# ESP32_Display-1_28-V1_0.net
KiCad netlist of a schematic drawn in EAGLE
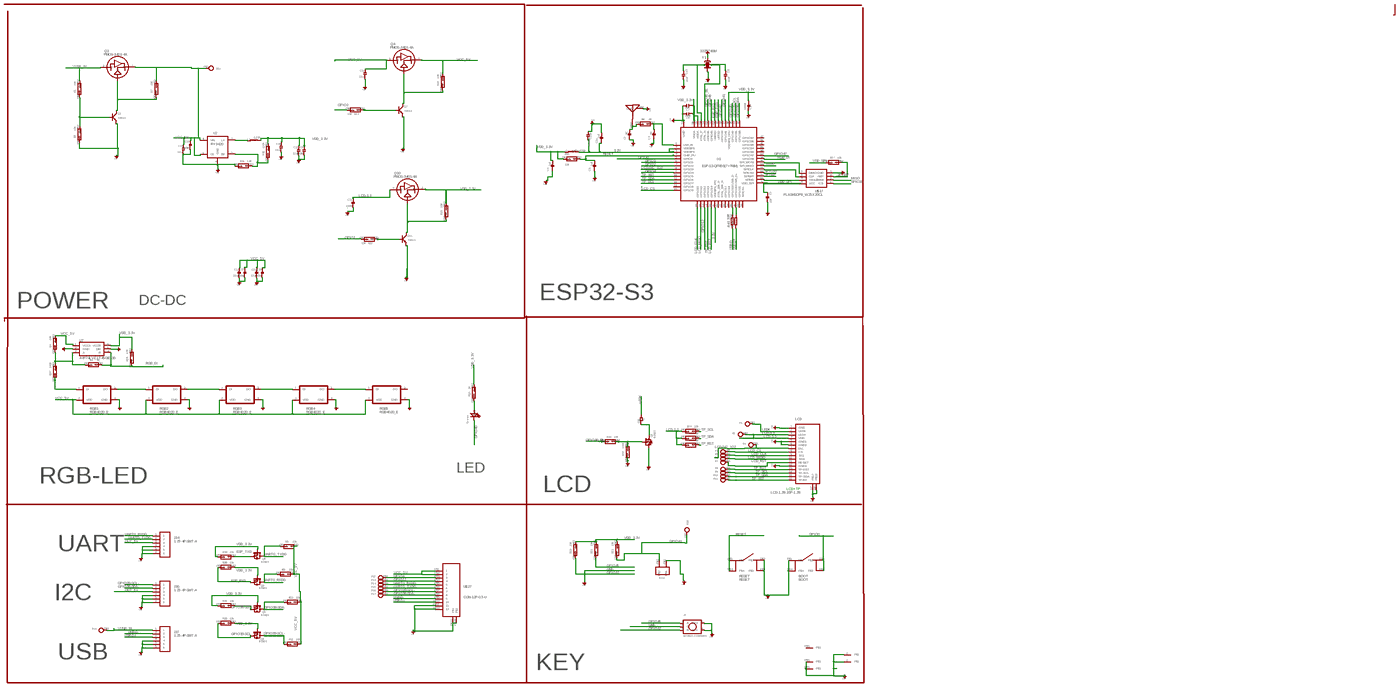
[diagram p0: schematic, sheet 1, overview]
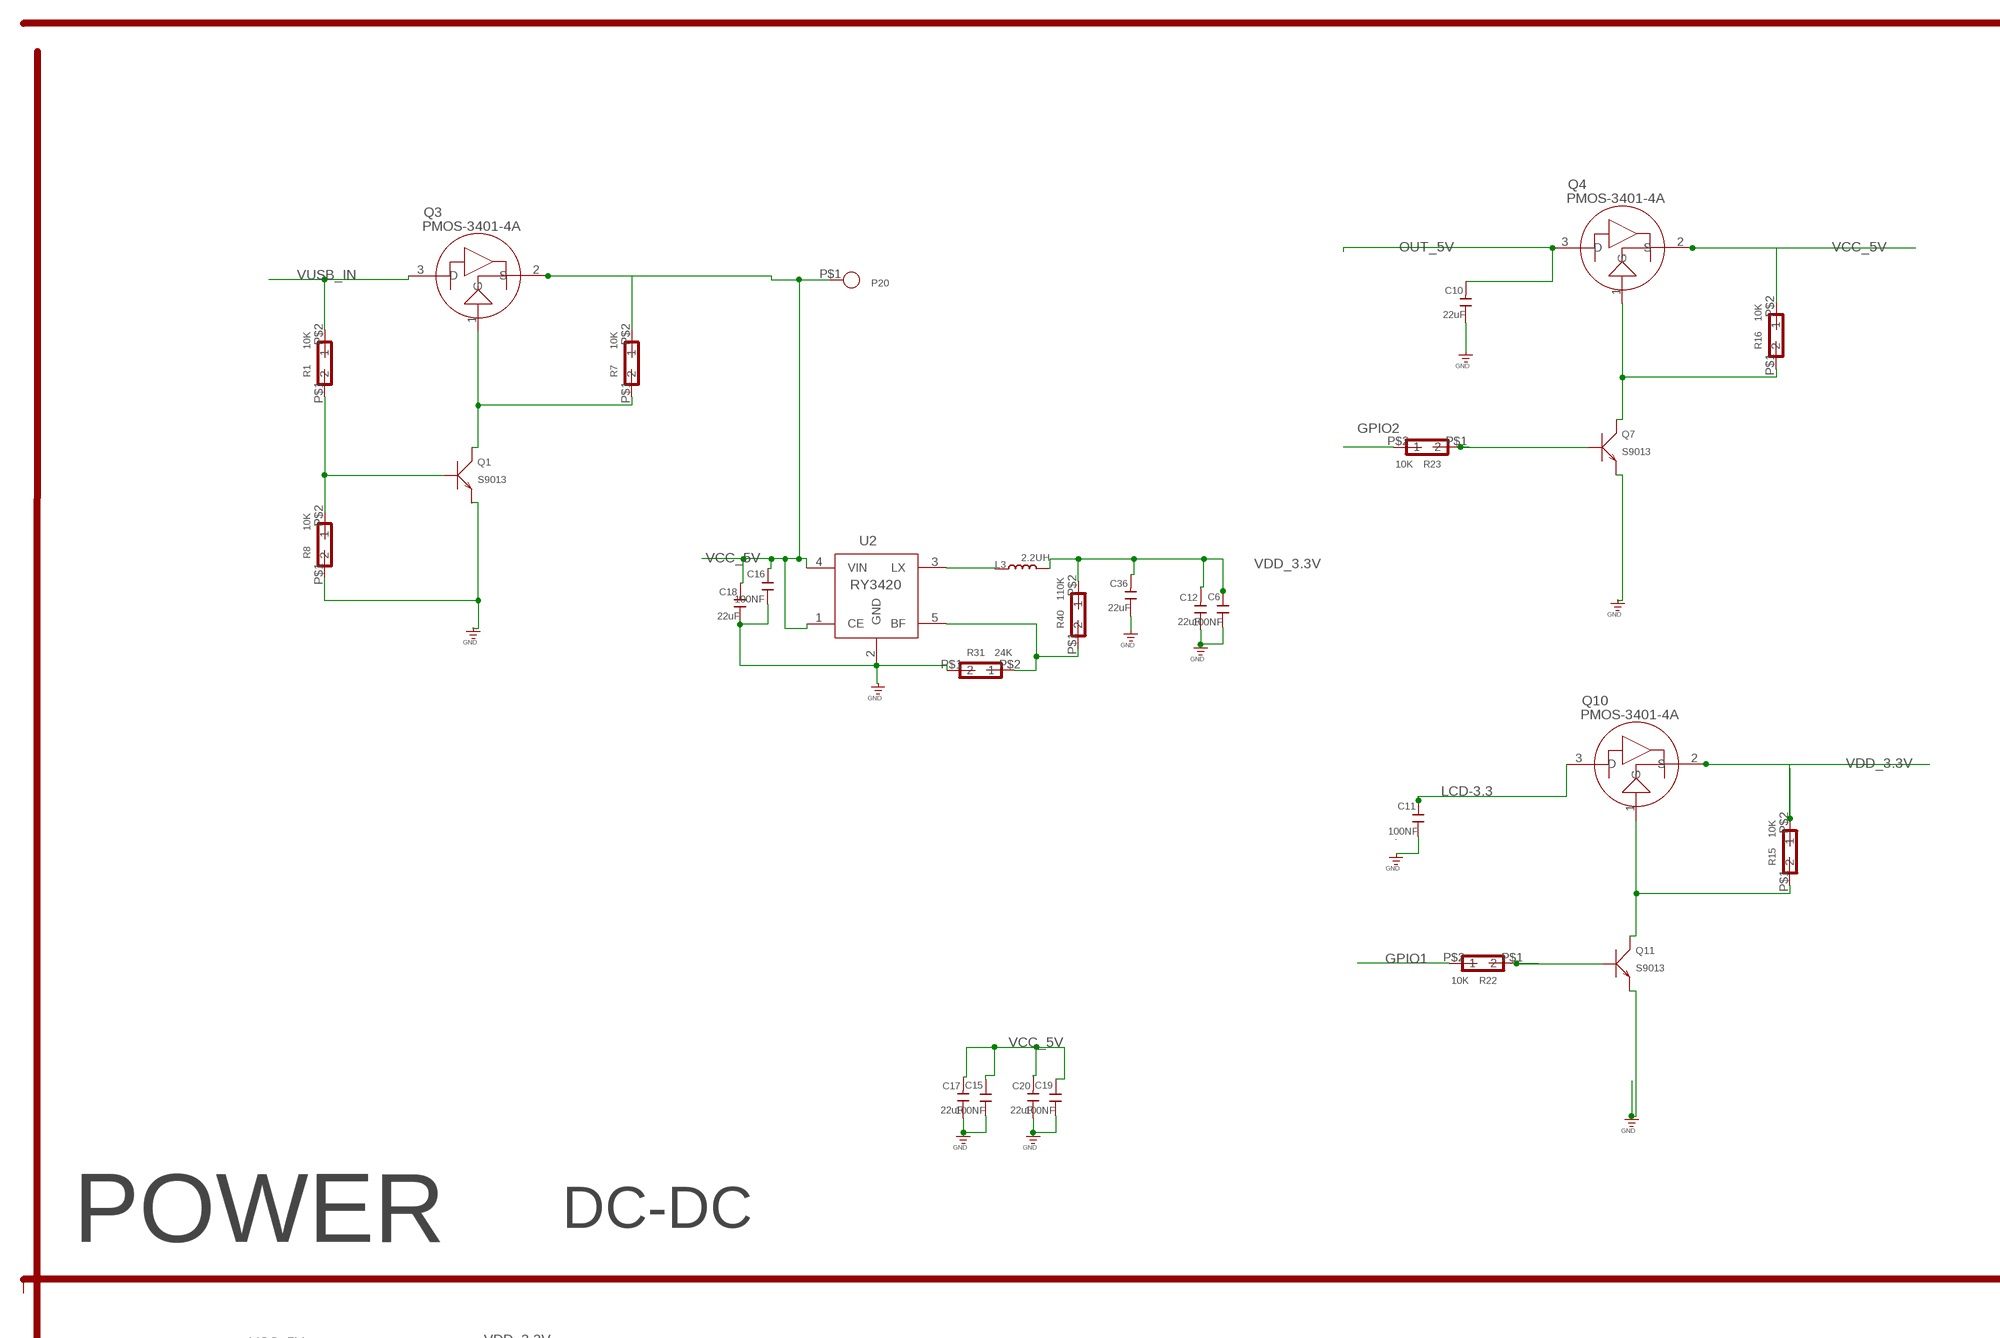
[diagram p1: schematic, sheet 1, part 1 of 5]
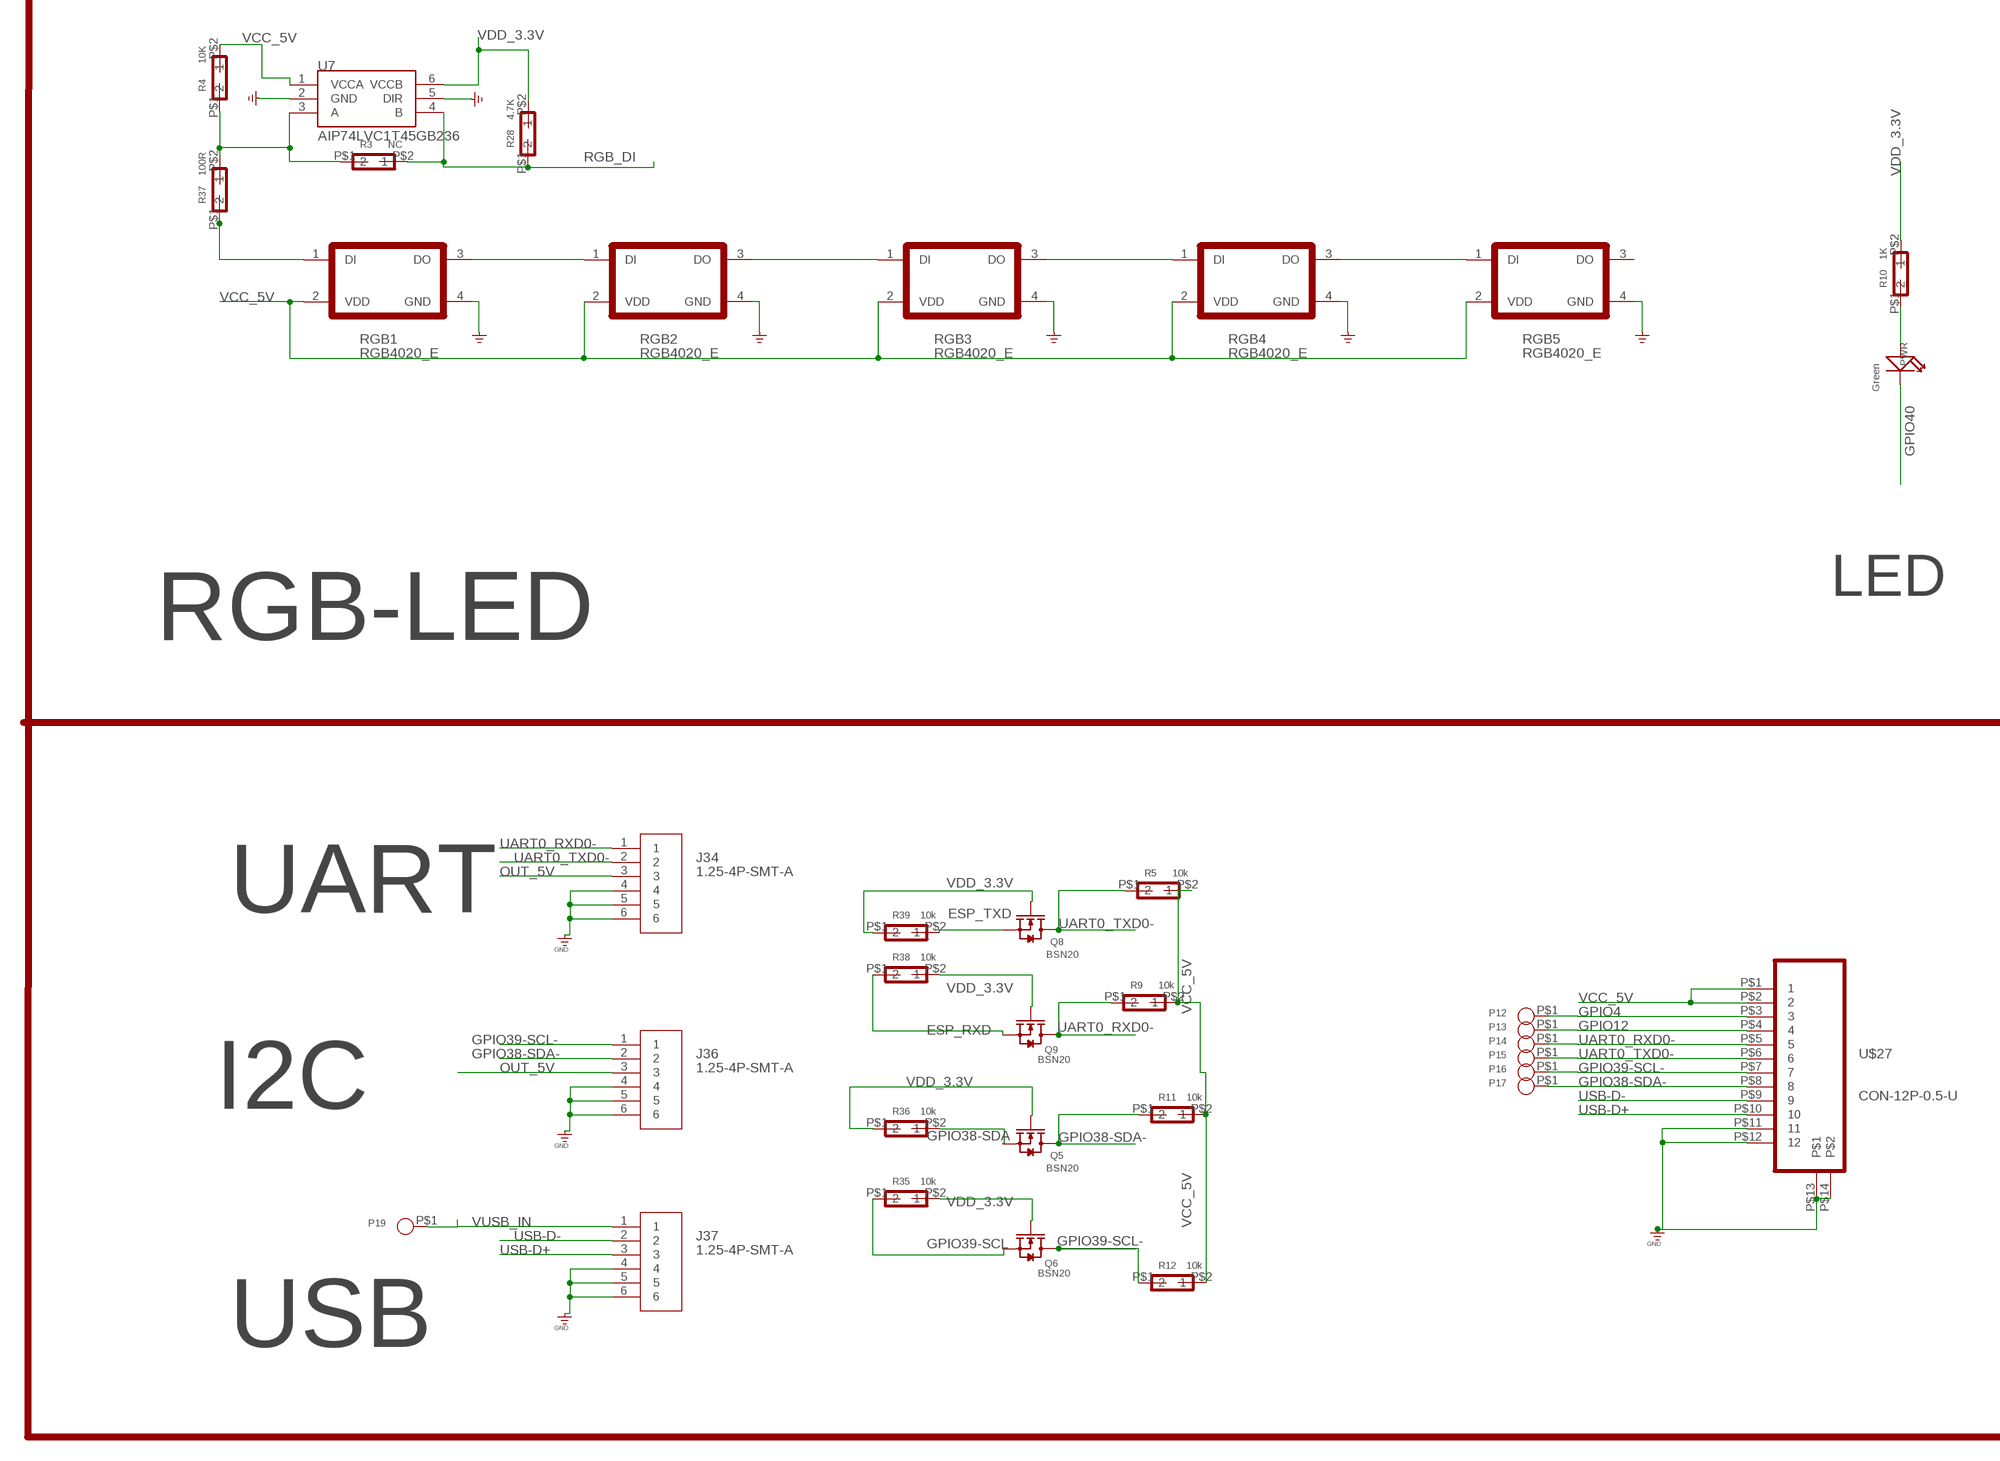
[diagram p2: schematic, sheet 1, part 2 of 5]
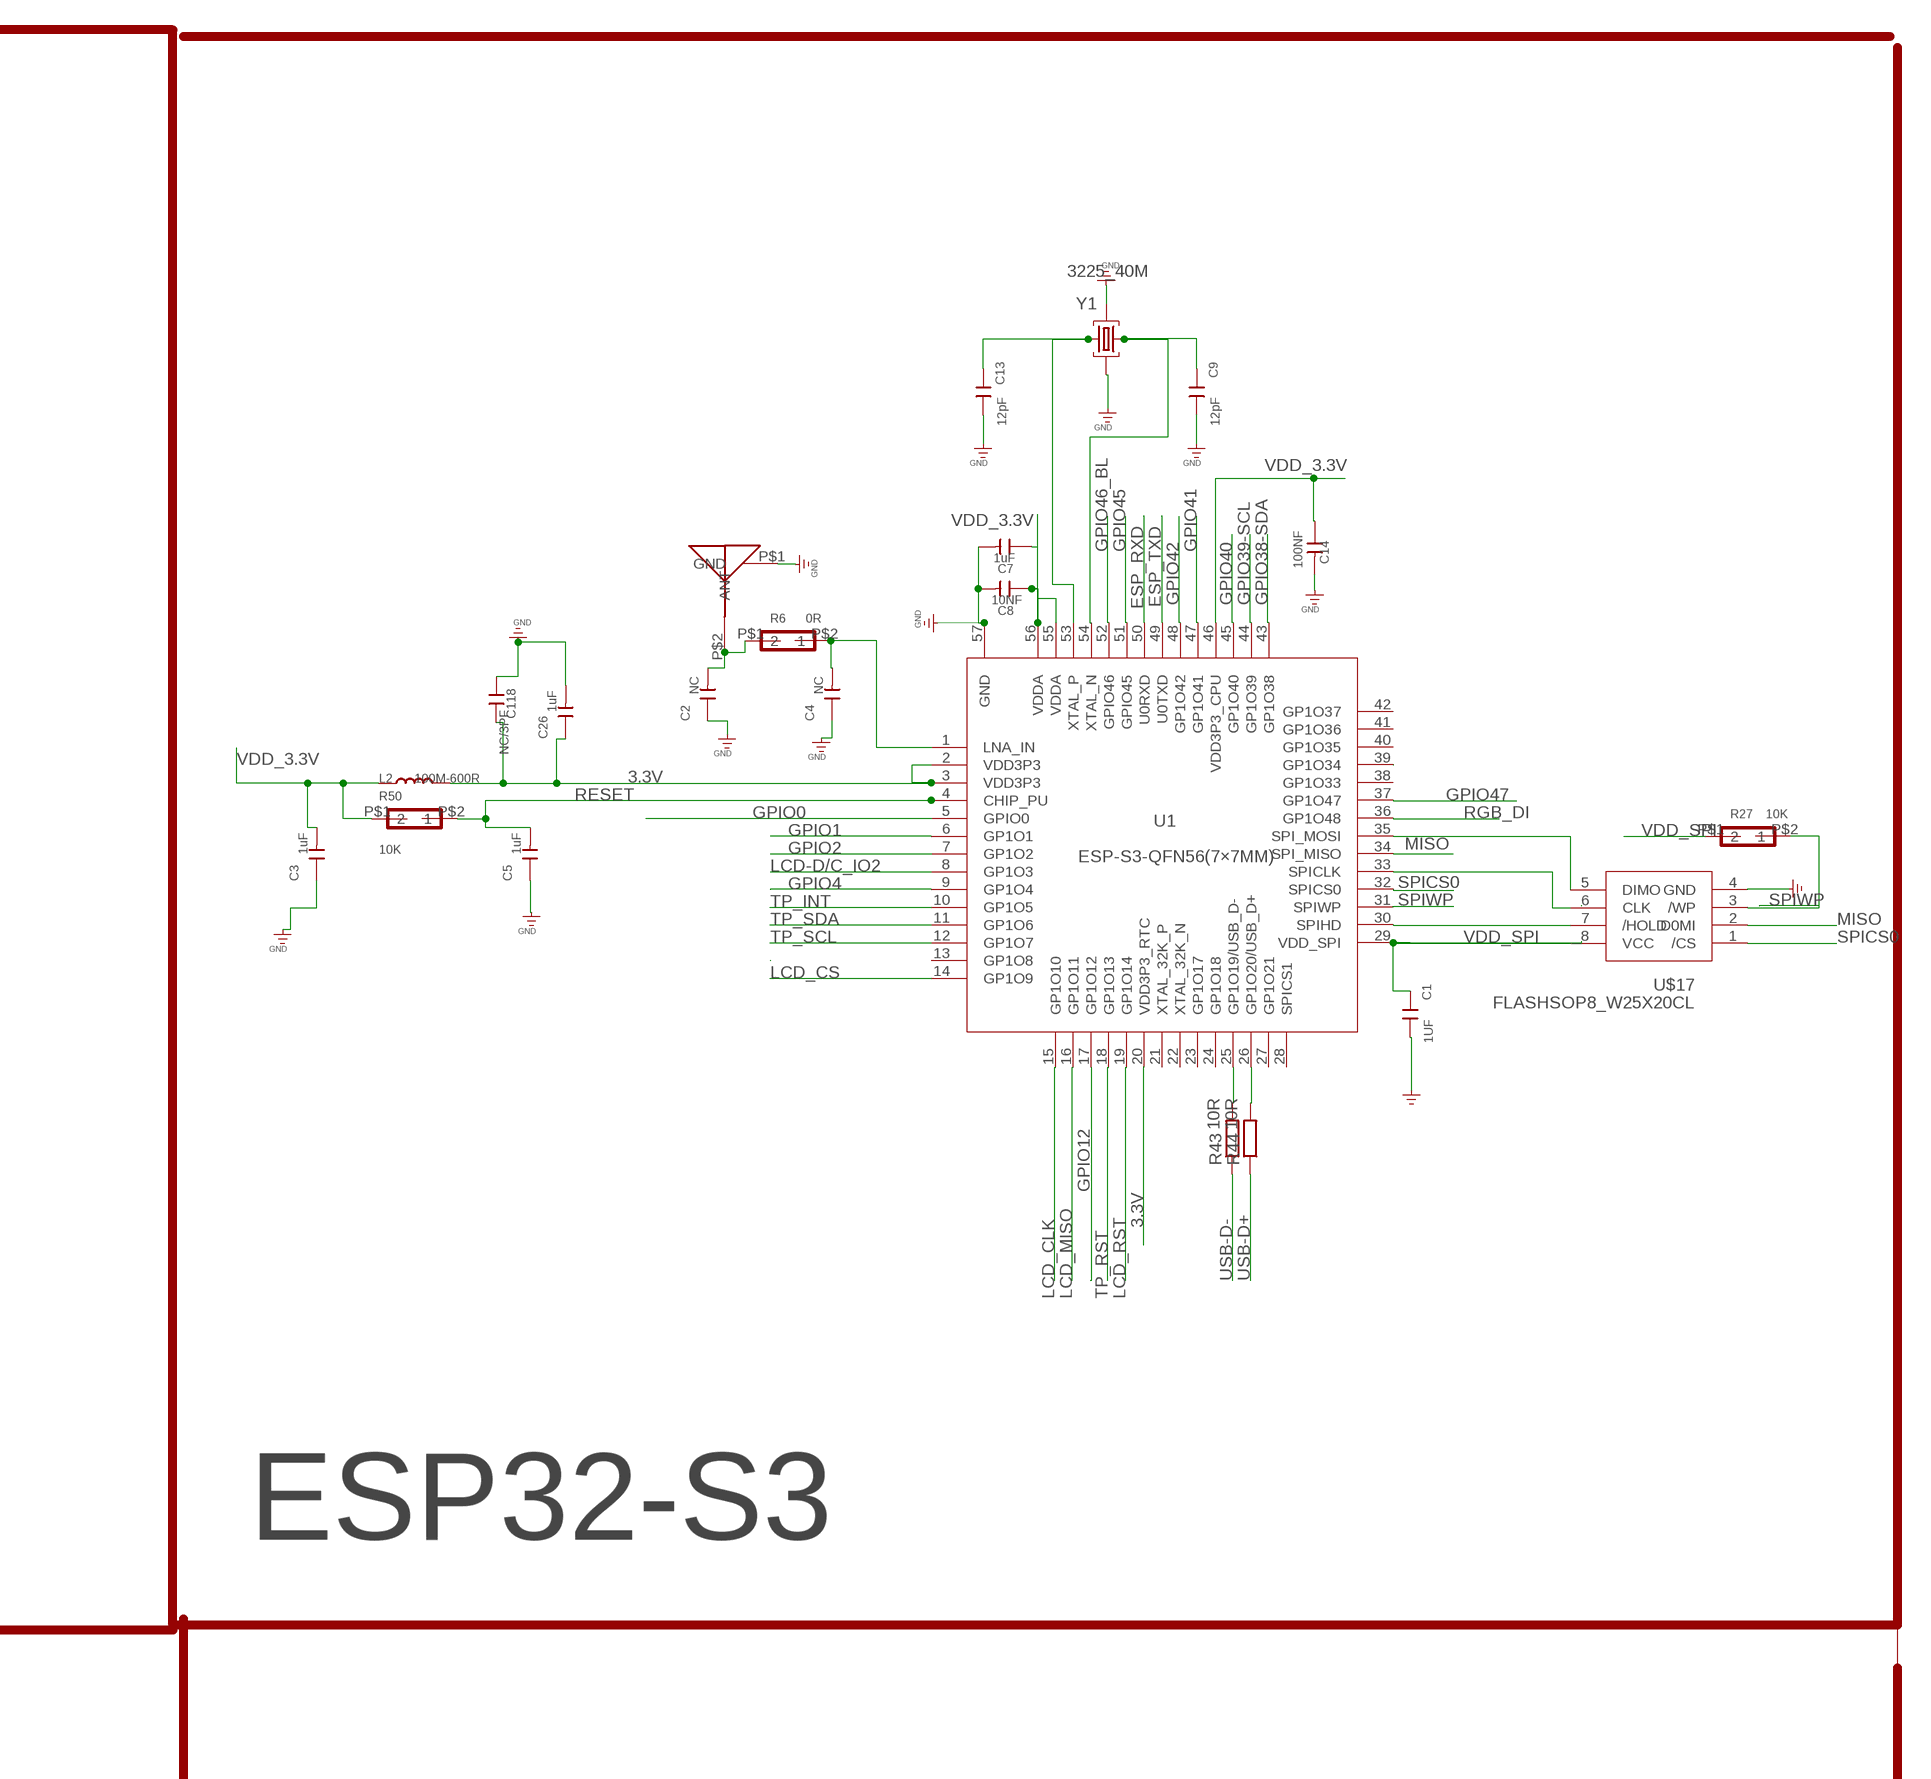
[diagram p3: schematic, sheet 1, part 3 of 5]
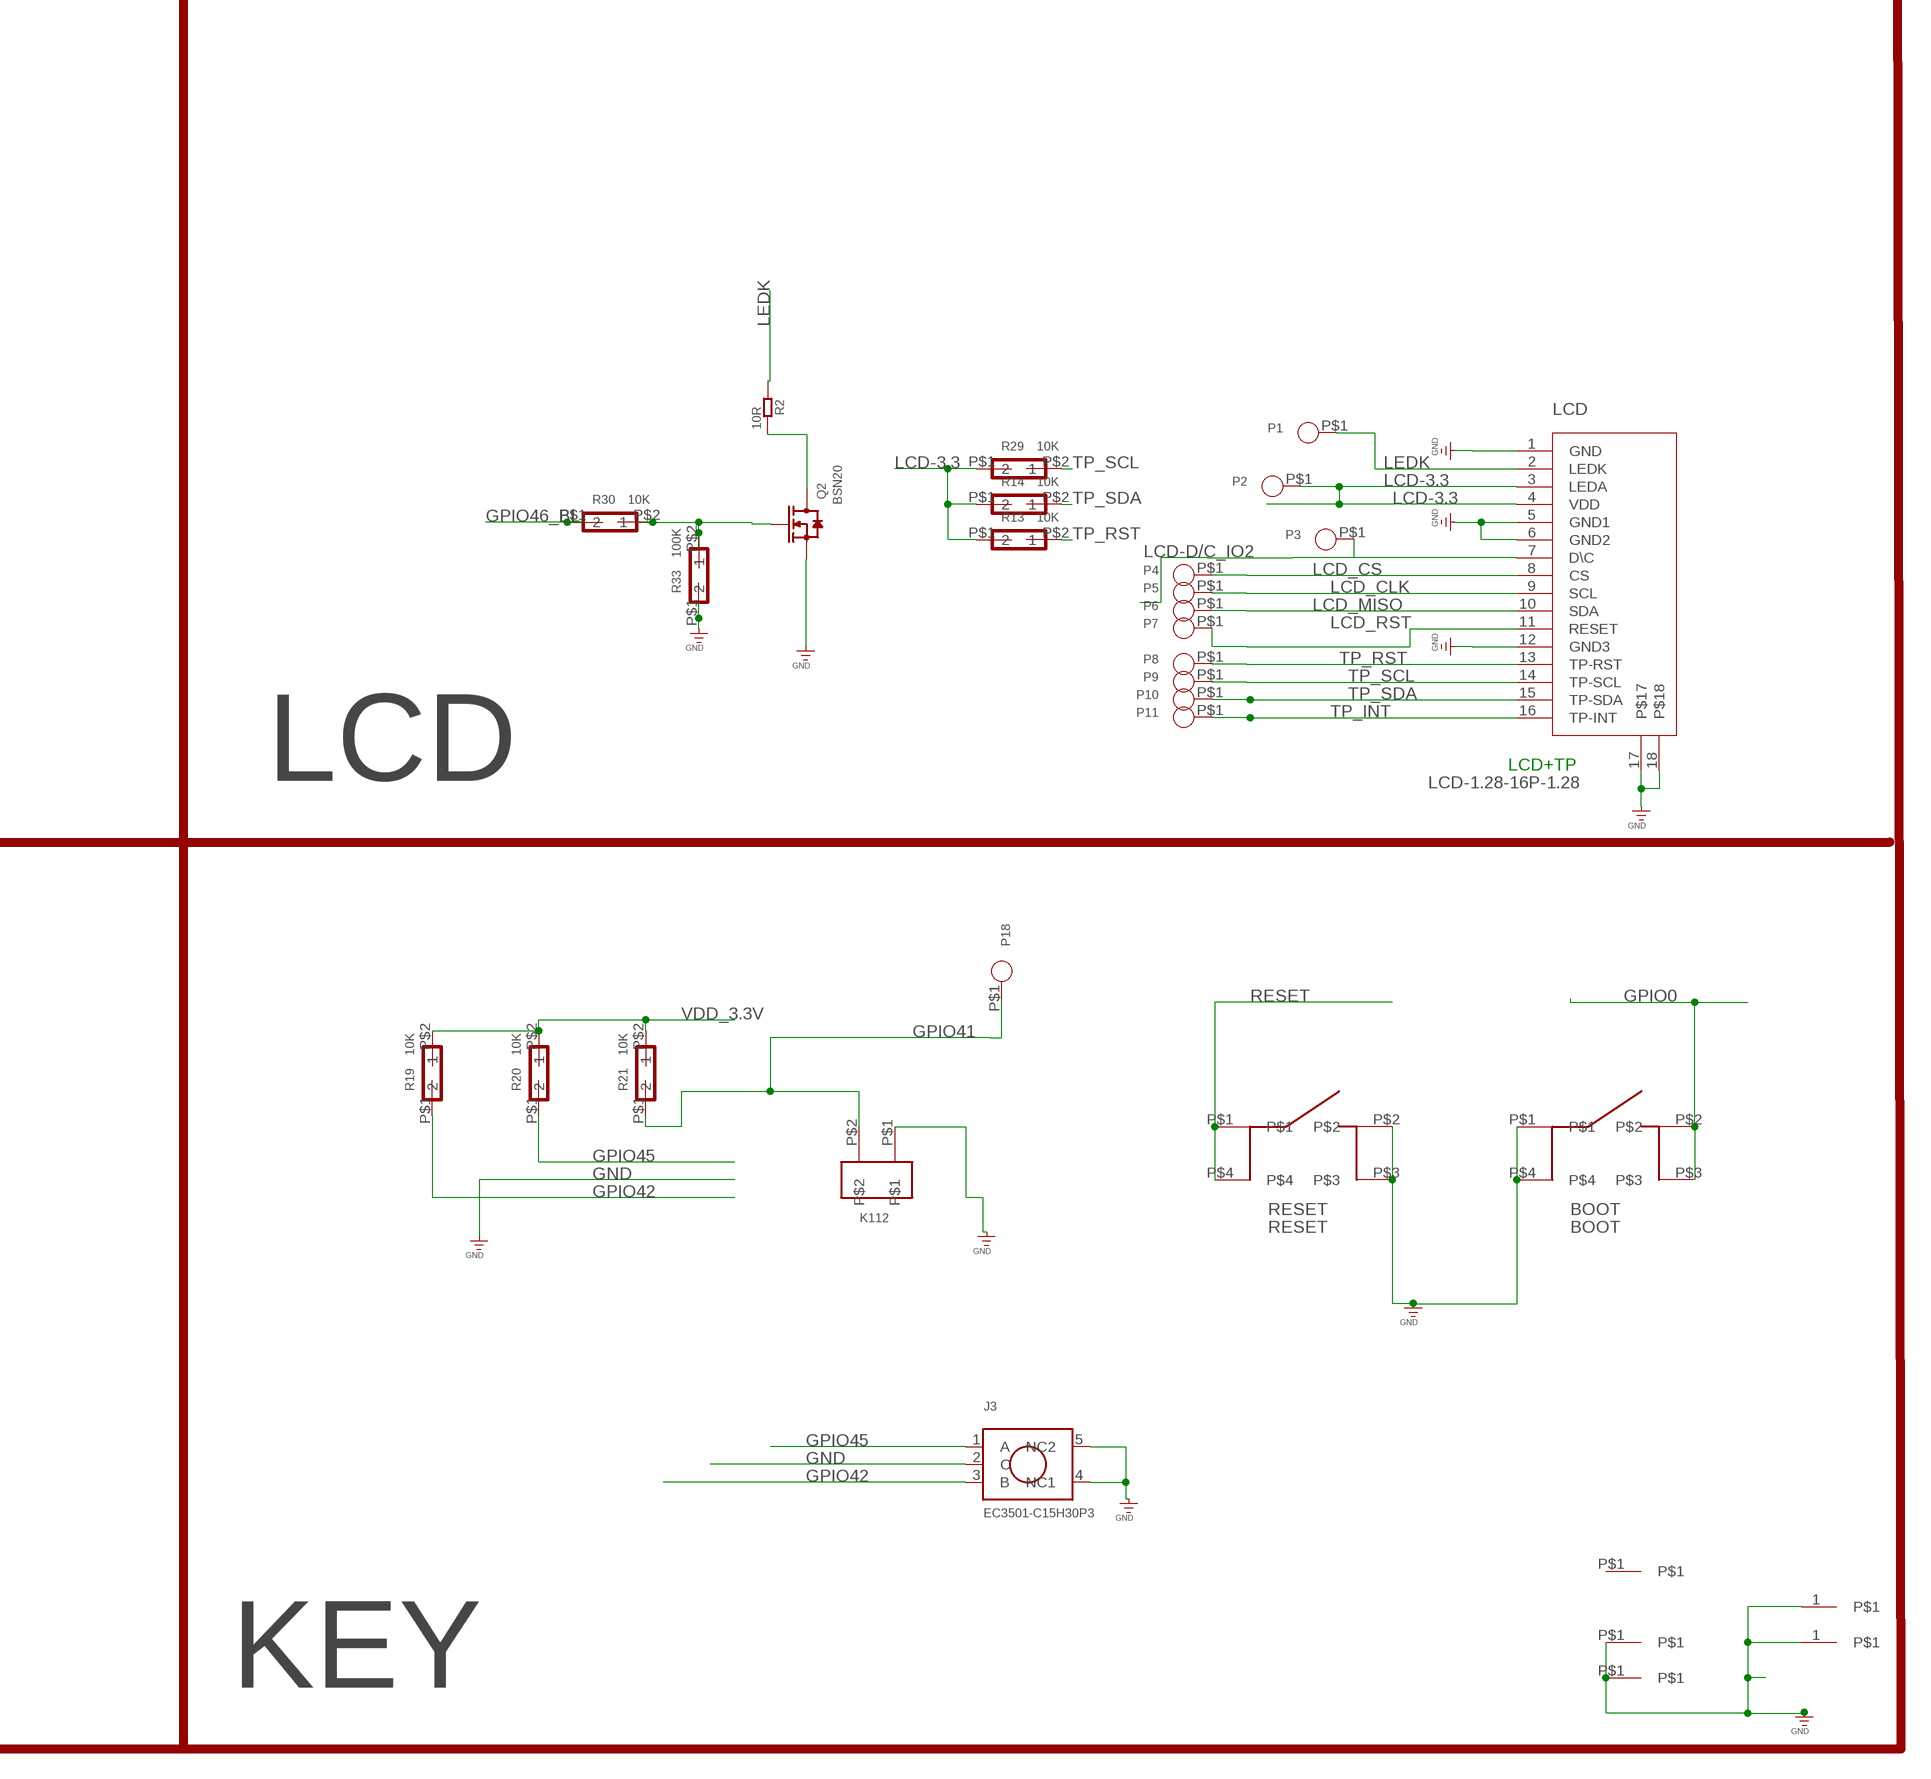
[diagram p4: schematic, sheet 1, part 4 of 5]
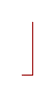
[diagram p5: schematic, sheet 1, part 5 of 5]

(export (version "E")
  (design (tool "Eeschema 10.0.6"))
  (components
    (comp (ref "ANT")
      (value "BT_ANT")
      (footprint "eagle-import:BT_ANT")
      (libsource (lib "eagle-import") (part "BT_ANT"))
    )
    (comp (ref "BOOT")
      (value "BOOT")
      (footprint "eagle-import:SW-4.5_4.5")
      (libsource (lib "eagle-import") (part "SW-4"))
    )
    (comp (ref "C1")
      (value "1UF")
      (footprint "eagle-import:0402")
      (libsource (lib "eagle-import") (part "C0402_W"))
    )
    (comp (ref "C2")
      (value "NC")
      (footprint "eagle-import:C0402")
      (libsource (lib "eagle-import") (part "CAPC0402-1"))
    )
    (comp (ref "C3")
      (value "1uF")
      (footprint "eagle-import:C0402")
      (libsource (lib "eagle-import") (part "CAPC0402-1"))
    )
    (comp (ref "C4")
      (value "NC")
      (footprint "eagle-import:C0402")
      (libsource (lib "eagle-import") (part "CAPC0402-1"))
    )
    (comp (ref "C5")
      (value "1uF")
      (footprint "eagle-import:C0402")
      (libsource (lib "eagle-import") (part "CAPC0402-1"))
    )
    (comp (ref "C6")
      (value "100NF")
      (footprint "eagle-import:0603")
      (libsource (lib "eagle-import") (part "C0603"))
    )
    (comp (ref "C7")
      (value "1uF")
      (footprint "eagle-import:C0603")
      (libsource (lib "eagle-import") (part "C-0603"))
    )
    (comp (ref "C8")
      (value "10NF")
      (footprint "eagle-import:C0603")
      (libsource (lib "eagle-import") (part "C-0603"))
    )
    (comp (ref "C9")
      (value "12pF")
      (footprint "eagle-import:0402")
      (libsource (lib "eagle-import") (part "C0402_W"))
    )
    (comp (ref "C10")
      (value "22uF")
      (footprint "eagle-import:0805")
      (libsource (lib "eagle-import") (part "C0805"))
    )
    (comp (ref "C11")
      (value "100NF")
      (footprint "eagle-import:0603")
      (libsource (lib "eagle-import") (part "C0603"))
    )
    (comp (ref "C12")
      (value "22uF")
      (footprint "eagle-import:0805")
      (libsource (lib "eagle-import") (part "C0805"))
    )
    (comp (ref "C13")
      (value "12pF")
      (footprint "eagle-import:0402")
      (libsource (lib "eagle-import") (part "C0402_W"))
    )
    (comp (ref "C14")
      (value "100NF")
      (footprint "eagle-import:C0603")
      (libsource (lib "eagle-import") (part "C-0603"))
    )
    (comp (ref "C15")
      (value "100NF")
      (footprint "eagle-import:0603")
      (libsource (lib "eagle-import") (part "C0603"))
    )
    (comp (ref "C16")
      (value "100NF")
      (footprint "eagle-import:0603")
      (libsource (lib "eagle-import") (part "C0603"))
    )
    (comp (ref "C17")
      (value "22uF")
      (footprint "eagle-import:0805")
      (libsource (lib "eagle-import") (part "C0805"))
    )
    (comp (ref "C18")
      (value "22uF")
      (footprint "eagle-import:0805")
      (libsource (lib "eagle-import") (part "C0805"))
    )
    (comp (ref "C19")
      (value "100NF")
      (footprint "eagle-import:0603")
      (libsource (lib "eagle-import") (part "C0603"))
    )
    (comp (ref "C20")
      (value "22uF")
      (footprint "eagle-import:0805")
      (libsource (lib "eagle-import") (part "C0805"))
    )
    (comp (ref "C26")
      (value "1uF")
      (footprint "eagle-import:C0402")
      (libsource (lib "eagle-import") (part "CAPC0402-1"))
    )
    (comp (ref "C36")
      (value "22uF")
      (footprint "eagle-import:0805")
      (libsource (lib "eagle-import") (part "C0805"))
    )
    (comp (ref "C118")
      (value "NC/3PF")
      (footprint "eagle-import:0603")
      (libsource (lib "eagle-import") (part "C0603"))
    )
    (comp (ref "J3")
      (value "EC3501-C15H30P3")
      (footprint "eagle-import:EC3501-C15H30P3")
      (libsource (lib "eagle-import") (part "EC3501-C15H30P3"))
    )
    (comp (ref "J34")
      (value "1.25-4P-SMT-A")
      (footprint "eagle-import:1.25-4P立贴")
      (libsource (lib "eagle-import") (part "1.25-4P-SMT-A"))
    )
    (comp (ref "J36")
      (value "1.25-4P-SMT-A")
      (footprint "eagle-import:1.25-4P立贴")
      (libsource (lib "eagle-import") (part "1.25-4P-SMT-A"))
    )
    (comp (ref "J37")
      (value "1.25-4P-SMT-A")
      (footprint "eagle-import:1.25-4P立贴")
      (libsource (lib "eagle-import") (part "1.25-4P-SMT-A"))
    )
    (comp (ref "K112")
      (value "BUTTON_2P")
      (footprint "eagle-import:BUTTON_2P")
      (libsource (lib "eagle-import") (part "BUTTON_2P"))
    )
    (comp (ref "L2")
      (value "100M-600R")
      (footprint "eagle-import:L0603")
      (libsource (lib "eagle-import") (part "L0603"))
    )
    (comp (ref "L3")
      (value "2.2UH")
      (footprint "eagle-import:L0420")
      (libsource (lib "eagle-import") (part "LL0420"))
    )
    (comp (ref "LCD")
      (value "LCD-1.28-16P-1.28")
      (footprint "eagle-import:0.5MM-16P")
      (libsource (lib "eagle-import") (part "LCD-1.28-16P-1.28"))
    )
    (comp (ref "P1")
      (value "PADPAD-1.0MM")
      (footprint "eagle-import:PAD-1.0MM")
      (libsource (lib "eagle-import") (part "PADPAD-1.0MM"))
    )
    (comp (ref "P2")
      (value "PADPAD-1.0MM")
      (footprint "eagle-import:PAD-1.0MM")
      (libsource (lib "eagle-import") (part "PADPAD-1.0MM"))
    )
    (comp (ref "P3")
      (value "PADPAD-1.0MM")
      (footprint "eagle-import:PAD-1.0MM")
      (libsource (lib "eagle-import") (part "PADPAD-1.0MM"))
    )
    (comp (ref "P4")
      (value "PADPAD-1.0MM")
      (footprint "eagle-import:PAD-1.0MM")
      (libsource (lib "eagle-import") (part "PADPAD-1.0MM"))
    )
    (comp (ref "P5")
      (value "PADPAD-1.0MM")
      (footprint "eagle-import:PAD-1.0MM")
      (libsource (lib "eagle-import") (part "PADPAD-1.0MM"))
    )
    (comp (ref "P6")
      (value "PADPAD-1.0MM")
      (footprint "eagle-import:PAD-1.0MM")
      (libsource (lib "eagle-import") (part "PADPAD-1.0MM"))
    )
    (comp (ref "P7")
      (value "PADPAD-1.0MM")
      (footprint "eagle-import:PAD-1.0MM")
      (libsource (lib "eagle-import") (part "PADPAD-1.0MM"))
    )
    (comp (ref "P8")
      (value "PADPAD-1.0MM")
      (footprint "eagle-import:PAD-1.0MM")
      (libsource (lib "eagle-import") (part "PADPAD-1.0MM"))
    )
    (comp (ref "P9")
      (value "PADPAD-1.0MM")
      (footprint "eagle-import:PAD-1.0MM")
      (libsource (lib "eagle-import") (part "PADPAD-1.0MM"))
    )
    (comp (ref "P10")
      (value "PADPAD-1.0MM")
      (footprint "eagle-import:PAD-1.0MM")
      (libsource (lib "eagle-import") (part "PADPAD-1.0MM"))
    )
    (comp (ref "P11")
      (value "PADPAD-1.0MM")
      (footprint "eagle-import:PAD-1.0MM")
      (libsource (lib "eagle-import") (part "PADPAD-1.0MM"))
    )
    (comp (ref "P12")
      (value "PADPAD-1.0MM")
      (footprint "eagle-import:PAD-1.0MM")
      (libsource (lib "eagle-import") (part "PADPAD-1.0MM"))
    )
    (comp (ref "P13")
      (value "PADPAD-1.0MM")
      (footprint "eagle-import:PAD-1.0MM")
      (libsource (lib "eagle-import") (part "PADPAD-1.0MM"))
    )
    (comp (ref "P14")
      (value "PADPAD-1.0MM")
      (footprint "eagle-import:PAD-1.0MM")
      (libsource (lib "eagle-import") (part "PADPAD-1.0MM"))
    )
    (comp (ref "P15")
      (value "PADPAD-1.0MM")
      (footprint "eagle-import:PAD-1.0MM")
      (libsource (lib "eagle-import") (part "PADPAD-1.0MM"))
    )
    (comp (ref "P16")
      (value "PADPAD-1.0MM")
      (footprint "eagle-import:PAD-1.0MM")
      (libsource (lib "eagle-import") (part "PADPAD-1.0MM"))
    )
    (comp (ref "P17")
      (value "PADPAD-1.0MM")
      (footprint "eagle-import:PAD-1.0MM")
      (libsource (lib "eagle-import") (part "PADPAD-1.0MM"))
    )
    (comp (ref "P18")
      (value "PADPAD-1.0MM")
      (footprint "eagle-import:PAD-1.0MM")
      (libsource (lib "eagle-import") (part "PADPAD-1.0MM"))
    )
    (comp (ref "P19")
      (value "PADPAD-1.0MM")
      (footprint "eagle-import:PAD-1.0MM")
      (libsource (lib "eagle-import") (part "PADPAD-1.0MM"))
    )
    (comp (ref "P20")
      (value "PADPAD-1.0MM")
      (footprint "eagle-import:PAD-1.0MM")
      (libsource (lib "eagle-import") (part "PADPAD-1.0MM"))
    )
    (comp (ref "PWR")
      (value "Green")
      (footprint "eagle-import:LED-0603")
      (libsource (lib "eagle-import") (part "LED'0603'"))
    )
    (comp (ref "Q1")
      (value "S9013")
      (footprint "eagle-import:SOT23@1")
      (libsource (lib "eagle-import") (part "TRANSISTOR-NPN-SOT23"))
    )
    (comp (ref "Q2")
      (value "BSN20")
      (footprint "eagle-import:SOT23")
      (libsource (lib "eagle-import") (part "MOSFET-N'SOT23'"))
    )
    (comp (ref "Q3")
      (value "PMOS-3401-4A")
      (footprint "eagle-import:SOT-23")
      (libsource (lib "eagle-import") (part "P-MOS-SOT23"))
    )
    (comp (ref "Q4")
      (value "PMOS-3401-4A")
      (footprint "eagle-import:SOT-23")
      (libsource (lib "eagle-import") (part "P-MOS-SOT23"))
    )
    (comp (ref "Q5")
      (value "BSN20")
      (footprint "eagle-import:SOT23")
      (libsource (lib "eagle-import") (part "MOSFET-N'SOT23'"))
    )
    (comp (ref "Q6")
      (value "BSN20")
      (footprint "eagle-import:SOT23")
      (libsource (lib "eagle-import") (part "MOSFET-N'SOT23'"))
    )
    (comp (ref "Q7")
      (value "S9013")
      (footprint "eagle-import:SOT23@1")
      (libsource (lib "eagle-import") (part "TRANSISTOR-NPN-SOT23"))
    )
    (comp (ref "Q8")
      (value "BSN20")
      (footprint "eagle-import:SOT23")
      (libsource (lib "eagle-import") (part "MOSFET-N'SOT23'"))
    )
    (comp (ref "Q9")
      (value "BSN20")
      (footprint "eagle-import:SOT23")
      (libsource (lib "eagle-import") (part "MOSFET-N'SOT23'"))
    )
    (comp (ref "Q10")
      (value "PMOS-3401-4A")
      (footprint "eagle-import:SOT-23")
      (libsource (lib "eagle-import") (part "P-MOS-SOT23"))
    )
    (comp (ref "Q11")
      (value "S9013")
      (footprint "eagle-import:SOT23@1")
      (libsource (lib "eagle-import") (part "TRANSISTOR-NPN-SOT23"))
    )
    (comp (ref "R1")
      (value "10K")
      (footprint "eagle-import:0402")
      (libsource (lib "eagle-import") (part "R0402"))
    )
    (comp (ref "R2")
      (value "10R")
      (footprint "eagle-import:R0603")
      (libsource (lib "eagle-import") (part "R0603"))
    )
    (comp (ref "R3")
      (value "NC")
      (footprint "eagle-import:0402")
      (libsource (lib "eagle-import") (part "R0402"))
    )
    (comp (ref "R4")
      (value "10K")
      (footprint "eagle-import:0402")
      (libsource (lib "eagle-import") (part "R0402"))
    )
    (comp (ref "R5")
      (value "10k")
      (footprint "eagle-import:0402")
      (libsource (lib "eagle-import") (part "R0402"))
    )
    (comp (ref "R6")
      (value "0R")
      (footprint "eagle-import:0402")
      (libsource (lib "eagle-import") (part "R0402"))
    )
    (comp (ref "R7")
      (value "10K")
      (footprint "eagle-import:0402")
      (libsource (lib "eagle-import") (part "R0402"))
    )
    (comp (ref "R8")
      (value "10K")
      (footprint "eagle-import:0402")
      (libsource (lib "eagle-import") (part "R0402"))
    )
    (comp (ref "R9")
      (value "10k")
      (footprint "eagle-import:0402")
      (libsource (lib "eagle-import") (part "R0402"))
    )
    (comp (ref "R10")
      (value "1K")
      (footprint "eagle-import:0402")
      (libsource (lib "eagle-import") (part "R0402"))
    )
    (comp (ref "R11")
      (value "10k")
      (footprint "eagle-import:0402")
      (libsource (lib "eagle-import") (part "R0402"))
    )
    (comp (ref "R12")
      (value "10k")
      (footprint "eagle-import:0402")
      (libsource (lib "eagle-import") (part "R0402"))
    )
    (comp (ref "R13")
      (value "10K")
      (footprint "eagle-import:0402")
      (libsource (lib "eagle-import") (part "R0402"))
    )
    (comp (ref "R14")
      (value "10K")
      (footprint "eagle-import:0402")
      (libsource (lib "eagle-import") (part "R0402"))
    )
    (comp (ref "R15")
      (value "10K")
      (footprint "eagle-import:0402")
      (libsource (lib "eagle-import") (part "R0402"))
    )
    (comp (ref "R16")
      (value "10K")
      (footprint "eagle-import:0402")
      (libsource (lib "eagle-import") (part "R0402"))
    )
    (comp (ref "R19")
      (value "10K")
      (footprint "eagle-import:0402")
      (libsource (lib "eagle-import") (part "R0402"))
    )
    (comp (ref "R20")
      (value "10K")
      (footprint "eagle-import:0402")
      (libsource (lib "eagle-import") (part "R0402"))
    )
    (comp (ref "R21")
      (value "10K")
      (footprint "eagle-import:0402")
      (libsource (lib "eagle-import") (part "R0402"))
    )
    (comp (ref "R22")
      (value "10K")
      (footprint "eagle-import:0402")
      (libsource (lib "eagle-import") (part "R0402"))
    )
    (comp (ref "R23")
      (value "10K")
      (footprint "eagle-import:0402")
      (libsource (lib "eagle-import") (part "R0402"))
    )
    (comp (ref "R27")
      (value "10K")
      (footprint "eagle-import:0402")
      (libsource (lib "eagle-import") (part "R0402"))
    )
    (comp (ref "R28")
      (value "4.7K")
      (footprint "eagle-import:0402")
      (libsource (lib "eagle-import") (part "R0402"))
    )
    (comp (ref "R29")
      (value "10K")
      (footprint "eagle-import:0402")
      (libsource (lib "eagle-import") (part "R0402"))
    )
    (comp (ref "R30")
      (value "10K")
      (footprint "eagle-import:0402")
      (libsource (lib "eagle-import") (part "R0402"))
    )
    (comp (ref "R31")
      (value "24K")
      (footprint "eagle-import:0402")
      (libsource (lib "eagle-import") (part "R0402"))
    )
    (comp (ref "R33")
      (value "100K")
      (footprint "eagle-import:0402")
      (libsource (lib "eagle-import") (part "R0402"))
    )
    (comp (ref "R35")
      (value "10k")
      (footprint "eagle-import:0402")
      (libsource (lib "eagle-import") (part "R0402"))
    )
    (comp (ref "R36")
      (value "10k")
      (footprint "eagle-import:0402")
      (libsource (lib "eagle-import") (part "R0402"))
    )
    (comp (ref "R37")
      (value "100R")
      (footprint "eagle-import:0402")
      (libsource (lib "eagle-import") (part "R0402"))
    )
    (comp (ref "R38")
      (value "10k")
      (footprint "eagle-import:0402")
      (libsource (lib "eagle-import") (part "R0402"))
    )
    (comp (ref "R39")
      (value "10k")
      (footprint "eagle-import:0402")
      (libsource (lib "eagle-import") (part "R0402"))
    )
    (comp (ref "R40")
      (value "110K")
      (footprint "eagle-import:0402")
      (libsource (lib "eagle-import") (part "R0402"))
    )
    (comp (ref "R43")
      (value "10R")
      (footprint "eagle-import:R0402")
      (libsource (lib "eagle-import") (part "R-EU_R0402"))
    )
    (comp (ref "R44")
      (value "10R")
      (footprint "eagle-import:R0402")
      (libsource (lib "eagle-import") (part "R-EU_R0402"))
    )
    (comp (ref "R50")
      (value "10K")
      (footprint "eagle-import:0402")
      (libsource (lib "eagle-import") (part "R0402"))
    )
    (comp (ref "RESET")
      (value "RESET")
      (footprint "eagle-import:SW-4.5_4.5")
      (libsource (lib "eagle-import") (part "SW-4"))
    )
    (comp (ref "RGB1")
      (value "RGB4020_E")
      (footprint "eagle-import:RGB4020")
      (libsource (lib "eagle-import") (part "RGB4020_E"))
    )
    (comp (ref "RGB2")
      (value "RGB4020_E")
      (footprint "eagle-import:RGB4020")
      (libsource (lib "eagle-import") (part "RGB4020_E"))
    )
    (comp (ref "RGB3")
      (value "RGB4020_E")
      (footprint "eagle-import:RGB4020")
      (libsource (lib "eagle-import") (part "RGB4020_E"))
    )
    (comp (ref "RGB4")
      (value "RGB4020_E")
      (footprint "eagle-import:RGB4020")
      (libsource (lib "eagle-import") (part "RGB4020_E"))
    )
    (comp (ref "RGB5")
      (value "RGB4020_E")
      (footprint "eagle-import:RGB4020")
      (libsource (lib "eagle-import") (part "RGB4020_E"))
    )
    (comp (ref "T1")
      (value "T2.5-A")
      (footprint "eagle-import:T-2.5")
      (libsource (lib "eagle-import") (part "T2.5-A"))
    )
    (comp (ref "T2")
      (value "T2.5-A")
      (footprint "eagle-import:T-2.5")
      (libsource (lib "eagle-import") (part "T2.5-A"))
    )
    (comp (ref "U$17")
      (value "FLASHSOP8_W25X20CL")
      (footprint "eagle-import:FLASHSOP8_SOP8")
      (libsource (lib "eagle-import") (part "FLASHSOP8_W25X20CL"))
    )
    (comp (ref "U$27")
      (value "CON-12P-0.5-U")
      (footprint "eagle-import:CON-0.5-12P-U")
      (libsource (lib "eagle-import") (part "CON-12P-0.5-U"))
    )
    (comp (ref "U$28")
      (value "T-2-1.1")
      (footprint "eagle-import:T-2-1.1")
      (libsource (lib "eagle-import") (part "T-2-1.1"))
    )
    (comp (ref "U$30")
      (value "T-2-1.1")
      (footprint "eagle-import:T-2-1.1")
      (libsource (lib "eagle-import") (part "T-2-1.1"))
    )
    (comp (ref "U$31")
      (value "T-2-1.1")
      (footprint "eagle-import:T-2-1.1")
      (libsource (lib "eagle-import") (part "T-2-1.1"))
    )
    (comp (ref "U1")
      (value "ESP-S3-QFN56(7×7MM)")
      (footprint "eagle-import:ESP-S3-QFN56(7×7MM)")
      (libsource (lib "eagle-import") (part "ESP-S3-QFN56(7×7MM)"))
    )
    (comp (ref "U2")
      (value "RY3420")
      (footprint "eagle-import:SOT23-5")
      (libsource (lib "eagle-import") (part "HX3406"))
    )
    (comp (ref "U7")
      (value "AIP74LVC1T45GB236")
      (footprint "eagle-import:SOT23-6L")
      (libsource (lib "eagle-import") (part "AIP74LVC1T45GB236"))
    )
    (comp (ref "Y1")
      (value "3225_40M")
      (footprint "eagle-import:CRYSTAL-3.2-2.5")
      (libsource (lib "eagle-import") (part "CRYSTAL-3.2-2.5"))
    )
  )
  (nets
    (net (code "1") (name "/3.3V") (class "Default")
      (node (ref "C118") (pin "2") (pinfunction "2_2") (pintype "passive"))
      (node (ref "C26") (pin "1") (pinfunction "1_1") (pintype "passive"))
      (node (ref "L2") (pin "2") (pinfunction "2_2") (pintype "passive"))
      (node (ref "U1") (pin "2") (pinfunction "VDD3P3_2") (pintype "bidirectional"))
      (node (ref "U1") (pin "20") (pinfunction "VDD3P3_RTC_20") (pintype "bidirectional"))
      (node (ref "U1") (pin "3") (pinfunction "VDD3P3_3") (pintype "bidirectional"))
    )
    (net (code "2") (name "/ESP_RXD") (class "Default")
      (node (ref "Q9") (pin "2") (pinfunction "S_2") (pintype "passive"))
      (node (ref "R38") (pin "P$1") (pinfunction "1_P$1") (pintype "bidirectional"))
      (node (ref "U1") (pin "50") (pinfunction "U0RXD_50") (pintype "bidirectional"))
    )
    (net (code "3") (name "/ESP_TXD") (class "Default")
      (node (ref "Q8") (pin "2") (pinfunction "S_2") (pintype "passive"))
      (node (ref "R39") (pin "P$2") (pinfunction "2_P$2") (pintype "bidirectional"))
      (node (ref "U1") (pin "49") (pinfunction "U0TXD_49") (pintype "bidirectional"))
    )
    (net (code "4") (name "/GPIO0") (class "Default")
      (node (ref "BOOT") (pin "P$2") (pinfunction "P$2_P$2") (pintype "bidirectional"))
      (node (ref "BOOT") (pin "P$3") (pinfunction "P$3_P$3") (pintype "bidirectional"))
      (node (ref "U1") (pin "5") (pinfunction "GPIO0_5") (pintype "bidirectional"))
    )
    (net (code "5") (name "/GPIO1") (class "Default")
      (node (ref "R22") (pin "P$2") (pinfunction "2_P$2") (pintype "bidirectional"))
      (node (ref "U1") (pin "6") (pinfunction "GP1O1_6") (pintype "bidirectional"))
    )
    (net (code "6") (name "/GPIO2") (class "Default")
      (node (ref "R23") (pin "P$2") (pinfunction "2_P$2") (pintype "bidirectional"))
      (node (ref "U1") (pin "7") (pinfunction "GP1O2_7") (pintype "bidirectional"))
    )
    (net (code "7") (name "/GPIO4") (class "Default")
      (node (ref "P12") (pin "P$1") (pinfunction "P$1_P$1") (pintype "bidirectional"))
      (node (ref "U$27") (pin "P$3") (pinfunction "3_P$3") (pintype "bidirectional"))
      (node (ref "U1") (pin "9") (pinfunction "GP1O4_9") (pintype "bidirectional"))
    )
    (net (code "8") (name "/GPIO12") (class "Default")
      (node (ref "P13") (pin "P$1") (pinfunction "P$1_P$1") (pintype "bidirectional"))
      (node (ref "U$27") (pin "P$4") (pinfunction "4_P$4") (pintype "bidirectional"))
      (node (ref "U1") (pin "17") (pinfunction "GP1O12_17") (pintype "bidirectional"))
    )
    (net (code "9") (name "/GPIO38-SDA") (class "Default")
      (node (ref "Q5") (pin "2") (pinfunction "S_2") (pintype "passive"))
      (node (ref "R36") (pin "P$2") (pinfunction "2_P$2") (pintype "bidirectional"))
      (node (ref "U1") (pin "43") (pinfunction "GP1O38_43") (pintype "bidirectional"))
    )
    (net (code "10") (name "/GPIO38-SDA-") (class "Default")
      (node (ref "J36") (pin "2") (pinfunction "2_2") (pintype "bidirectional"))
      (node (ref "P17") (pin "P$1") (pinfunction "P$1_P$1") (pintype "bidirectional"))
      (node (ref "Q5") (pin "3") (pinfunction "D_3") (pintype "passive"))
      (node (ref "R11") (pin "P$1") (pinfunction "1_P$1") (pintype "bidirectional"))
      (node (ref "U$27") (pin "P$8") (pinfunction "8_P$8") (pintype "bidirectional"))
    )
    (net (code "11") (name "/GPIO39-SCL") (class "Default")
      (node (ref "Q6") (pin "2") (pinfunction "S_2") (pintype "passive"))
      (node (ref "R35") (pin "P$1") (pinfunction "1_P$1") (pintype "bidirectional"))
      (node (ref "U1") (pin "44") (pinfunction "GP1O39_44") (pintype "bidirectional"))
    )
    (net (code "12") (name "/GPIO39-SCL-") (class "Default")
      (node (ref "J36") (pin "1") (pinfunction "1_1") (pintype "bidirectional"))
      (node (ref "P16") (pin "P$1") (pinfunction "P$1_P$1") (pintype "bidirectional"))
      (node (ref "Q6") (pin "3") (pinfunction "D_3") (pintype "passive"))
      (node (ref "R12") (pin "P$1") (pinfunction "1_P$1") (pintype "bidirectional"))
      (node (ref "U$27") (pin "P$7") (pinfunction "7_P$7") (pintype "bidirectional"))
    )
    (net (code "13") (name "/GPIO40") (class "Default")
      (node (ref "PWR") (pin "-") (pinfunction "-_-") (pintype "passive"))
      (node (ref "U1") (pin "45") (pinfunction "GP1O40_45") (pintype "bidirectional"))
    )
    (net (code "14") (name "/GPIO41") (class "Default")
      (node (ref "K112") (pin "P$2") (pinfunction "P$2_P$2") (pintype "bidirectional"))
      (node (ref "P18") (pin "P$1") (pinfunction "P$1_P$1") (pintype "bidirectional"))
      (node (ref "R21") (pin "P$1") (pinfunction "1_P$1") (pintype "bidirectional"))
      (node (ref "U1") (pin "47") (pinfunction "GP1O41_47") (pintype "bidirectional"))
    )
    (net (code "15") (name "/GPIO42") (class "Default")
      (node (ref "J3") (pin "3") (pinfunction "B_3") (pintype "bidirectional"))
      (node (ref "R19") (pin "P$1") (pinfunction "1_P$1") (pintype "bidirectional"))
      (node (ref "U1") (pin "48") (pinfunction "GP1O42_48") (pintype "bidirectional"))
    )
    (net (code "16") (name "/GPIO45") (class "Default")
      (node (ref "J3") (pin "1") (pinfunction "A_1") (pintype "bidirectional"))
      (node (ref "R20") (pin "P$1") (pinfunction "1_P$1") (pintype "bidirectional"))
      (node (ref "U1") (pin "51") (pinfunction "GPIO45_51") (pintype "bidirectional"))
    )
    (net (code "17") (name "/GPIO46_BL") (class "Default")
      (node (ref "R30") (pin "P$1") (pinfunction "1_P$1") (pintype "bidirectional"))
      (node (ref "U1") (pin "52") (pinfunction "GPIO46_52") (pintype "bidirectional"))
    )
    (net (code "18") (name "/GPIO47") (class "Default")
      (node (ref "U1") (pin "37") (pinfunction "GP1O47_37") (pintype "bidirectional"))
    )
    (net (code "19") (name "/LCD-3.3") (class "Default")
      (node (ref "C11") (pin "1") (pinfunction "1_1") (pintype "passive"))
      (node (ref "LCD") (pin "3") (pinfunction "LEDA_3") (pintype "bidirectional"))
      (node (ref "LCD") (pin "4") (pinfunction "VDD_4") (pintype "bidirectional"))
      (node (ref "P2") (pin "P$1") (pinfunction "P$1_P$1") (pintype "bidirectional"))
      (node (ref "Q10") (pin "3") (pinfunction "D_3") (pintype "bidirectional"))
      (node (ref "R13") (pin "P$1") (pinfunction "1_P$1") (pintype "bidirectional"))
      (node (ref "R14") (pin "P$1") (pinfunction "1_P$1") (pintype "bidirectional"))
      (node (ref "R29") (pin "P$1") (pinfunction "1_P$1") (pintype "bidirectional"))
    )
    (net (code "20") (name "/LCD-D{slash}C_IO2") (class "Default")
      (node (ref "LCD") (pin "7") (pinfunction "D\\C_7") (pintype "bidirectional"))
      (node (ref "P3") (pin "P$1") (pinfunction "P$1_P$1") (pintype "bidirectional"))
      (node (ref "U1") (pin "8") (pinfunction "GP1O3_8") (pintype "bidirectional"))
    )
    (net (code "21") (name "/LCD_CLK") (class "Default")
      (node (ref "LCD") (pin "9") (pinfunction "SCL_9") (pintype "bidirectional"))
      (node (ref "P5") (pin "P$1") (pinfunction "P$1_P$1") (pintype "bidirectional"))
      (node (ref "U1") (pin "15") (pinfunction "GP1O10_15") (pintype "bidirectional"))
    )
    (net (code "22") (name "/LCD_CS") (class "Default")
      (node (ref "LCD") (pin "8") (pinfunction "CS_8") (pintype "bidirectional"))
      (node (ref "P4") (pin "P$1") (pinfunction "P$1_P$1") (pintype "bidirectional"))
      (node (ref "U1") (pin "14") (pinfunction "GP1O9_14") (pintype "bidirectional"))
    )
    (net (code "23") (name "/LCD_MISO") (class "Default")
      (node (ref "LCD") (pin "10") (pinfunction "SDA_10") (pintype "bidirectional"))
      (node (ref "P6") (pin "P$1") (pinfunction "P$1_P$1") (pintype "bidirectional"))
      (node (ref "U1") (pin "16") (pinfunction "GP1O11_16") (pintype "bidirectional"))
    )
    (net (code "24") (name "/LCD_RST") (class "Default")
      (node (ref "LCD") (pin "11") (pinfunction "RESET_11") (pintype "bidirectional"))
      (node (ref "P7") (pin "P$1") (pinfunction "P$1_P$1") (pintype "bidirectional"))
      (node (ref "U1") (pin "19") (pinfunction "GP1O14_19") (pintype "bidirectional"))
    )
    (net (code "25") (name "/LEDK") (class "Default")
      (node (ref "LCD") (pin "2") (pinfunction "LEDK_2") (pintype "bidirectional"))
      (node (ref "P1") (pin "P$1") (pinfunction "P$1_P$1") (pintype "bidirectional"))
      (node (ref "R2") (pin "2") (pinfunction "2_2") (pintype "passive"))
    )
    (net (code "26") (name "/MISO") (class "Default")
      (node (ref "U$17") (pin "2") (pinfunction "D0MI_2") (pintype "output"))
      (node (ref "U1") (pin "34") (pinfunction "SPI_MISO_34") (pintype "bidirectional"))
    )
    (net (code "27") (name "/OUT_5V") (class "Default")
      (node (ref "C10") (pin "2") (pinfunction "2_2") (pintype "passive"))
      (node (ref "J34") (pin "3") (pinfunction "3_3") (pintype "bidirectional"))
      (node (ref "J36") (pin "3") (pinfunction "3_3") (pintype "bidirectional"))
      (node (ref "Q4") (pin "3") (pinfunction "D_3") (pintype "bidirectional"))
    )
    (net (code "28") (name "/RESET") (class "Default")
      (node (ref "C5") (pin "2") (pinfunction "2_2") (pintype "passive"))
      (node (ref "R50") (pin "P$2") (pinfunction "2_P$2") (pintype "bidirectional"))
      (node (ref "RESET") (pin "P$1") (pinfunction "P$1_P$1") (pintype "bidirectional"))
      (node (ref "RESET") (pin "P$4") (pinfunction "P$4_P$4") (pintype "bidirectional"))
      (node (ref "U1") (pin "4") (pinfunction "CHIP_PU_4") (pintype "bidirectional"))
    )
    (net (code "29") (name "/RGB_DI") (class "Default")
      (node (ref "R28") (pin "P$1") (pinfunction "1_P$1") (pintype "bidirectional"))
      (node (ref "R3") (pin "P$2") (pinfunction "2_P$2") (pintype "bidirectional"))
      (node (ref "U1") (pin "36") (pinfunction "GP1O48_36") (pintype "bidirectional"))
      (node (ref "U7") (pin "4") (pinfunction "B_4") (pintype "bidirectional"))
    )
    (net (code "30") (name "/SPICS0") (class "Default")
      (node (ref "U$17") (pin "1") (pinfunction "/CS_1") (pintype "bidirectional"))
      (node (ref "U1") (pin "32") (pinfunction "SPICS0_32") (pintype "bidirectional"))
    )
    (net (code "31") (name "/SPIWP") (class "Default")
      (node (ref "R27") (pin "P$2") (pinfunction "2_P$2") (pintype "bidirectional"))
      (node (ref "U$17") (pin "3") (pinfunction "/WP_3") (pintype "bidirectional"))
      (node (ref "U1") (pin "31") (pinfunction "SPIWP_31") (pintype "bidirectional"))
    )
    (net (code "32") (name "/TP_INT") (class "Default")
      (node (ref "LCD") (pin "16") (pinfunction "TP-INT_16") (pintype "bidirectional"))
      (node (ref "P11") (pin "P$1") (pinfunction "P$1_P$1") (pintype "bidirectional"))
      (node (ref "U1") (pin "10") (pinfunction "GP1O5_10") (pintype "bidirectional"))
    )
    (net (code "33") (name "/TP_RST") (class "Default")
      (node (ref "LCD") (pin "13") (pinfunction "TP-RST_13") (pintype "bidirectional"))
      (node (ref "P8") (pin "P$1") (pinfunction "P$1_P$1") (pintype "bidirectional"))
      (node (ref "R13") (pin "P$2") (pinfunction "2_P$2") (pintype "bidirectional"))
      (node (ref "U1") (pin "18") (pinfunction "GP1O13_18") (pintype "bidirectional"))
    )
    (net (code "34") (name "/TP_SCL") (class "Default")
      (node (ref "LCD") (pin "14") (pinfunction "TP-SCL_14") (pintype "bidirectional"))
      (node (ref "P9") (pin "P$1") (pinfunction "P$1_P$1") (pintype "bidirectional"))
      (node (ref "R29") (pin "P$2") (pinfunction "2_P$2") (pintype "bidirectional"))
      (node (ref "U1") (pin "12") (pinfunction "GP1O7_12") (pintype "bidirectional"))
    )
    (net (code "35") (name "/TP_SDA") (class "Default")
      (node (ref "LCD") (pin "15") (pinfunction "TP-SDA_15") (pintype "bidirectional"))
      (node (ref "P10") (pin "P$1") (pinfunction "P$1_P$1") (pintype "bidirectional"))
      (node (ref "R14") (pin "P$2") (pinfunction "2_P$2") (pintype "bidirectional"))
      (node (ref "U1") (pin "11") (pinfunction "GP1O6_11") (pintype "bidirectional"))
    )
    (net (code "36") (name "/UART0_RXD0-") (class "Default")
      (node (ref "J34") (pin "1") (pinfunction "1_1") (pintype "bidirectional"))
      (node (ref "P14") (pin "P$1") (pinfunction "P$1_P$1") (pintype "bidirectional"))
      (node (ref "Q9") (pin "3") (pinfunction "D_3") (pintype "passive"))
      (node (ref "R9") (pin "P$1") (pinfunction "1_P$1") (pintype "bidirectional"))
      (node (ref "U$27") (pin "P$5") (pinfunction "5_P$5") (pintype "bidirectional"))
    )
    (net (code "37") (name "/UART0_TXD0-") (class "Default")
      (node (ref "J34") (pin "2") (pinfunction "2_2") (pintype "bidirectional"))
      (node (ref "P15") (pin "P$1") (pinfunction "P$1_P$1") (pintype "bidirectional"))
      (node (ref "Q8") (pin "3") (pinfunction "D_3") (pintype "passive"))
      (node (ref "R5") (pin "P$1") (pinfunction "1_P$1") (pintype "bidirectional"))
      (node (ref "U$27") (pin "P$6") (pinfunction "6_P$6") (pintype "bidirectional"))
    )
    (net (code "38") (name "/USB-D+") (class "Default")
      (node (ref "J37") (pin "3") (pinfunction "3_3") (pintype "bidirectional"))
      (node (ref "R44") (pin "1") (pinfunction "1_1") (pintype "passive"))
      (node (ref "U$27") (pin "P$10") (pinfunction "10_P$10") (pintype "bidirectional"))
    )
    (net (code "39") (name "/USB-D-") (class "Default")
      (node (ref "J37") (pin "2") (pinfunction "2_2") (pintype "bidirectional"))
      (node (ref "R43") (pin "1") (pinfunction "1_1") (pintype "passive"))
      (node (ref "U$27") (pin "P$9") (pinfunction "9_P$9") (pintype "bidirectional"))
    )
    (net (code "40") (name "/VCC_5V") (class "Default")
      (node (ref "C15") (pin "1") (pinfunction "1_1") (pintype "passive"))
      (node (ref "C16") (pin "1") (pinfunction "1_1") (pintype "passive"))
      (node (ref "C17") (pin "2") (pinfunction "2_2") (pintype "passive"))
      (node (ref "C18") (pin "2") (pinfunction "2_2") (pintype "passive"))
      (node (ref "C19") (pin "1") (pinfunction "1_1") (pintype "passive"))
      (node (ref "C20") (pin "2") (pinfunction "2_2") (pintype "passive"))
      (node (ref "P20") (pin "P$1") (pinfunction "P$1_P$1") (pintype "bidirectional"))
      (node (ref "Q3") (pin "2") (pinfunction "S_2") (pintype "bidirectional"))
      (node (ref "Q4") (pin "2") (pinfunction "S_2") (pintype "bidirectional"))
      (node (ref "R11") (pin "P$2") (pinfunction "2_P$2") (pintype "bidirectional"))
      (node (ref "R12") (pin "P$2") (pinfunction "2_P$2") (pintype "bidirectional"))
      (node (ref "R16") (pin "P$2") (pinfunction "2_P$2") (pintype "bidirectional"))
      (node (ref "R4") (pin "P$2") (pinfunction "2_P$2") (pintype "bidirectional"))
      (node (ref "R5") (pin "P$2") (pinfunction "2_P$2") (pintype "bidirectional"))
      (node (ref "R7") (pin "P$2") (pinfunction "2_P$2") (pintype "bidirectional"))
      (node (ref "R9") (pin "P$2") (pinfunction "2_P$2") (pintype "bidirectional"))
      (node (ref "RGB1") (pin "2") (pinfunction "VDD_2") (pintype "bidirectional"))
      (node (ref "RGB2") (pin "2") (pinfunction "VDD_2") (pintype "bidirectional"))
      (node (ref "RGB3") (pin "2") (pinfunction "VDD_2") (pintype "bidirectional"))
      (node (ref "RGB4") (pin "2") (pinfunction "VDD_2") (pintype "bidirectional"))
      (node (ref "RGB5") (pin "2") (pinfunction "VDD_2") (pintype "bidirectional"))
      (node (ref "U$27") (pin "P$1") (pinfunction "1_P$1") (pintype "bidirectional"))
      (node (ref "U$27") (pin "P$2") (pinfunction "2_P$2") (pintype "bidirectional"))
      (node (ref "U2") (pin "1") (pinfunction "CE_1") (pintype "bidirectional"))
      (node (ref "U2") (pin "4") (pinfunction "VIN_4") (pintype "bidirectional"))
      (node (ref "U7") (pin "1") (pinfunction "VCCA_1") (pintype "bidirectional"))
    )
    (net (code "41") (name "/VDD_3.3V") (class "Default")
      (node (ref "C12") (pin "2") (pinfunction "2_2") (pintype "passive"))
      (node (ref "C14") (pin "1") (pinfunction "1_1") (pintype "passive"))
      (node (ref "C3") (pin "2") (pinfunction "2_2") (pintype "passive"))
      (node (ref "C36") (pin "2") (pinfunction "2_2") (pintype "passive"))
      (node (ref "C6") (pin "1") (pinfunction "1_1") (pintype "passive"))
      (node (ref "C7") (pin "1") (pinfunction "1_1") (pintype "passive"))
      (node (ref "C8") (pin "1") (pinfunction "1_1") (pintype "passive"))
      (node (ref "L2") (pin "1") (pinfunction "1_1") (pintype "passive"))
      (node (ref "L3") (pin "2") (pinfunction "2_2") (pintype "passive"))
      (node (ref "Q10") (pin "2") (pinfunction "S_2") (pintype "bidirectional"))
      (node (ref "Q5") (pin "1") (pinfunction "G_1") (pintype "passive"))
      (node (ref "Q6") (pin "1") (pinfunction "G_1") (pintype "passive"))
      (node (ref "Q8") (pin "1") (pinfunction "G_1") (pintype "passive"))
      (node (ref "Q9") (pin "1") (pinfunction "G_1") (pintype "passive"))
      (node (ref "R10") (pin "P$2") (pinfunction "2_P$2") (pintype "bidirectional"))
      (node (ref "R15") (pin "P$2") (pinfunction "2_P$2") (pintype "bidirectional"))
      (node (ref "R19") (pin "P$2") (pinfunction "2_P$2") (pintype "bidirectional"))
      (node (ref "R20") (pin "P$2") (pinfunction "2_P$2") (pintype "bidirectional"))
      (node (ref "R21") (pin "P$2") (pinfunction "2_P$2") (pintype "bidirectional"))
      (node (ref "R28") (pin "P$2") (pinfunction "2_P$2") (pintype "bidirectional"))
      (node (ref "R35") (pin "P$2") (pinfunction "2_P$2") (pintype "bidirectional"))
      (node (ref "R36") (pin "P$1") (pinfunction "1_P$1") (pintype "bidirectional"))
      (node (ref "R38") (pin "P$2") (pinfunction "2_P$2") (pintype "bidirectional"))
      (node (ref "R39") (pin "P$1") (pinfunction "1_P$1") (pintype "bidirectional"))
      (node (ref "R40") (pin "P$2") (pinfunction "2_P$2") (pintype "bidirectional"))
      (node (ref "R50") (pin "P$1") (pinfunction "1_P$1") (pintype "bidirectional"))
      (node (ref "U1") (pin "46") (pinfunction "VDD3P3_CPU_46") (pintype "bidirectional"))
      (node (ref "U1") (pin "55") (pinfunction "VDDA_55") (pintype "bidirectional"))
      (node (ref "U1") (pin "56") (pinfunction "VDDA_56") (pintype "bidirectional"))
      (node (ref "U7") (pin "6") (pinfunction "VCCB_6") (pintype "bidirectional"))
    )
    (net (code "42") (name "/VDD_SPI") (class "Default")
      (node (ref "C1") (pin "1") (pinfunction "1_1") (pintype "passive"))
      (node (ref "R27") (pin "P$1") (pinfunction "1_P$1") (pintype "bidirectional"))
      (node (ref "U$17") (pin "8") (pinfunction "VCC_8") (pintype "power_in"))
      (node (ref "U1") (pin "29") (pinfunction "VDD_SPI_29") (pintype "bidirectional"))
    )
    (net (code "43") (name "/VUSB_IN") (class "Default")
      (node (ref "J37") (pin "1") (pinfunction "1_1") (pintype "bidirectional"))
      (node (ref "P19") (pin "P$1") (pinfunction "P$1_P$1") (pintype "bidirectional"))
      (node (ref "Q3") (pin "3") (pinfunction "D_3") (pintype "bidirectional"))
      (node (ref "R1") (pin "P$2") (pinfunction "2_P$2") (pintype "bidirectional"))
    )
    (net (code "44") (name "GND") (class "Default")
      (node (ref "ANT") (pin "P$1") (pinfunction "GND_P$1") (pintype "bidirectional"))
      (node (ref "BOOT") (pin "P$1") (pinfunction "P$1_P$1") (pintype "bidirectional"))
      (node (ref "BOOT") (pin "P$4") (pinfunction "P$4_P$4") (pintype "bidirectional"))
      (node (ref "C1") (pin "2") (pinfunction "2_2") (pintype "passive"))
      (node (ref "C10") (pin "1") (pinfunction "1_1") (pintype "passive"))
      (node (ref "C11") (pin "2") (pinfunction "2_2") (pintype "passive"))
      (node (ref "C118") (pin "1") (pinfunction "1_1") (pintype "passive"))
      (node (ref "C12") (pin "1") (pinfunction "1_1") (pintype "passive"))
      (node (ref "C13") (pin "2") (pinfunction "2_2") (pintype "passive"))
      (node (ref "C14") (pin "2") (pinfunction "2_2") (pintype "passive"))
      (node (ref "C15") (pin "2") (pinfunction "2_2") (pintype "passive"))
      (node (ref "C16") (pin "2") (pinfunction "2_2") (pintype "passive"))
      (node (ref "C17") (pin "1") (pinfunction "1_1") (pintype "passive"))
      (node (ref "C18") (pin "1") (pinfunction "1_1") (pintype "passive"))
      (node (ref "C19") (pin "2") (pinfunction "2_2") (pintype "passive"))
      (node (ref "C2") (pin "1") (pinfunction "1_1") (pintype "passive"))
      (node (ref "C20") (pin "1") (pinfunction "1_1") (pintype "passive"))
      (node (ref "C26") (pin "2") (pinfunction "2_2") (pintype "passive"))
      (node (ref "C3") (pin "1") (pinfunction "1_1") (pintype "passive"))
      (node (ref "C36") (pin "1") (pinfunction "1_1") (pintype "passive"))
      (node (ref "C4") (pin "1") (pinfunction "1_1") (pintype "passive"))
      (node (ref "C5") (pin "1") (pinfunction "1_1") (pintype "passive"))
      (node (ref "C6") (pin "2") (pinfunction "2_2") (pintype "passive"))
      (node (ref "C7") (pin "2") (pinfunction "2_2") (pintype "passive"))
      (node (ref "C8") (pin "2") (pinfunction "2_2") (pintype "passive"))
      (node (ref "C9") (pin "2") (pinfunction "2_2") (pintype "passive"))
      (node (ref "J3") (pin "2") (pinfunction "C_2") (pintype "bidirectional"))
      (node (ref "J3") (pin "4") (pinfunction "NC1_4") (pintype "bidirectional"))
      (node (ref "J3") (pin "5") (pinfunction "NC2_5") (pintype "bidirectional"))
      (node (ref "J34") (pin "4") (pinfunction "4_4") (pintype "bidirectional"))
      (node (ref "J34") (pin "5") (pinfunction "5_5") (pintype "bidirectional"))
      (node (ref "J34") (pin "6") (pinfunction "6_6") (pintype "bidirectional"))
      (node (ref "J36") (pin "4") (pinfunction "4_4") (pintype "bidirectional"))
      (node (ref "J36") (pin "5") (pinfunction "5_5") (pintype "bidirectional"))
      (node (ref "J36") (pin "6") (pinfunction "6_6") (pintype "bidirectional"))
      (node (ref "J37") (pin "4") (pinfunction "4_4") (pintype "bidirectional"))
      (node (ref "J37") (pin "5") (pinfunction "5_5") (pintype "bidirectional"))
      (node (ref "J37") (pin "6") (pinfunction "6_6") (pintype "bidirectional"))
      (node (ref "K112") (pin "P$1") (pinfunction "P$1_P$1") (pintype "bidirectional"))
      (node (ref "LCD") (pin "1") (pinfunction "GND_1") (pintype "bidirectional"))
      (node (ref "LCD") (pin "12") (pinfunction "GND3_12") (pintype "bidirectional"))
      (node (ref "LCD") (pin "17") (pinfunction "P$17_17") (pintype "bidirectional"))
      (node (ref "LCD") (pin "18") (pinfunction "P$18_18") (pintype "bidirectional"))
      (node (ref "LCD") (pin "5") (pinfunction "GND1_5") (pintype "bidirectional"))
      (node (ref "LCD") (pin "6") (pinfunction "GND2_6") (pintype "bidirectional"))
      (node (ref "Q1") (pin "2") (pinfunction "E_2") (pintype "passive"))
      (node (ref "Q11") (pin "2") (pinfunction "E_2") (pintype "passive"))
      (node (ref "Q2") (pin "2") (pinfunction "S_2") (pintype "passive"))
      (node (ref "Q7") (pin "2") (pinfunction "E_2") (pintype "passive"))
      (node (ref "R31") (pin "P$1") (pinfunction "1_P$1") (pintype "bidirectional"))
      (node (ref "R33") (pin "P$1") (pinfunction "1_P$1") (pintype "bidirectional"))
      (node (ref "R8") (pin "P$1") (pinfunction "1_P$1") (pintype "bidirectional"))
      (node (ref "RESET") (pin "P$2") (pinfunction "P$2_P$2") (pintype "bidirectional"))
      (node (ref "RESET") (pin "P$3") (pinfunction "P$3_P$3") (pintype "bidirectional"))
      (node (ref "RGB1") (pin "4") (pinfunction "GND_4") (pintype "bidirectional"))
      (node (ref "RGB2") (pin "4") (pinfunction "GND_4") (pintype "bidirectional"))
      (node (ref "RGB3") (pin "4") (pinfunction "GND_4") (pintype "bidirectional"))
      (node (ref "RGB4") (pin "4") (pinfunction "GND_4") (pintype "bidirectional"))
      (node (ref "RGB5") (pin "4") (pinfunction "GND_4") (pintype "bidirectional"))
      (node (ref "T1") (pin "1") (pinfunction "P$1_1") (pintype "bidirectional"))
      (node (ref "T2") (pin "1") (pinfunction "P$1_1") (pintype "bidirectional"))
      (node (ref "U$17") (pin "4") (pinfunction "GND_4") (pintype "bidirectional"))
      (node (ref "U$27") (pin "P$11") (pinfunction "11_P$11") (pintype "bidirectional"))
      (node (ref "U$27") (pin "P$12") (pinfunction "12_P$12") (pintype "bidirectional"))
      (node (ref "U$27") (pin "P$13") (pinfunction "P$1_P$13") (pintype "bidirectional"))
      (node (ref "U$27") (pin "P$14") (pinfunction "P$2_P$14") (pintype "bidirectional"))
      (node (ref "U$28") (pin "P$1") (pinfunction "P$1_P$1") (pintype "bidirectional"))
      (node (ref "U$31") (pin "P$1") (pinfunction "P$1_P$1") (pintype "bidirectional"))
      (node (ref "U1") (pin "57") (pinfunction "GND_57") (pintype "bidirectional"))
      (node (ref "U2") (pin "2") (pinfunction "GND_2") (pintype "bidirectional"))
      (node (ref "U7") (pin "2") (pinfunction "GND_2") (pintype "bidirectional"))
      (node (ref "U7") (pin "5") (pinfunction "DIR_5") (pintype "bidirectional"))
      (node (ref "Y1") (pin "2") (pinfunction "GND_2") (pintype "passive"))
      (node (ref "Y1") (pin "4") (pinfunction "GND_4") (pintype "passive"))
    )
    (net (code "45") (name "Net-(ANT-ANT)") (class "Default")
      (node (ref "ANT") (pin "P$2") (pinfunction "ANT_P$2") (pintype "bidirectional"))
      (node (ref "C2") (pin "2") (pinfunction "2_2") (pintype "passive"))
      (node (ref "R6") (pin "P$1") (pinfunction "1_P$1") (pintype "bidirectional"))
    )
    (net (code "46") (name "Net-(Q1-B)") (class "Default")
      (node (ref "Q1") (pin "1") (pinfunction "B_1") (pintype "passive"))
      (node (ref "R1") (pin "P$1") (pinfunction "1_P$1") (pintype "bidirectional"))
      (node (ref "R8") (pin "P$2") (pinfunction "2_P$2") (pintype "bidirectional"))
    )
    (net (code "47") (name "Net-(Q1-C)") (class "Default")
      (node (ref "Q1") (pin "3") (pinfunction "C_3") (pintype "passive"))
      (node (ref "Q3") (pin "1") (pinfunction "G_1") (pintype "bidirectional"))
      (node (ref "R7") (pin "P$1") (pinfunction "1_P$1") (pintype "bidirectional"))
    )
    (net (code "48") (name "Net-(Q2-D)") (class "Default")
      (node (ref "Q2") (pin "3") (pinfunction "D_3") (pintype "passive"))
      (node (ref "R2") (pin "1") (pinfunction "1_1") (pintype "passive"))
    )
    (net (code "49") (name "Net-(Q2-G)") (class "Default")
      (node (ref "Q2") (pin "1") (pinfunction "G_1") (pintype "passive"))
      (node (ref "R30") (pin "P$2") (pinfunction "2_P$2") (pintype "bidirectional"))
      (node (ref "R33") (pin "P$2") (pinfunction "2_P$2") (pintype "bidirectional"))
    )
    (net (code "50") (name "Net-(Q4-G)") (class "Default")
      (node (ref "Q4") (pin "1") (pinfunction "G_1") (pintype "bidirectional"))
      (node (ref "Q7") (pin "3") (pinfunction "C_3") (pintype "passive"))
      (node (ref "R16") (pin "P$1") (pinfunction "1_P$1") (pintype "bidirectional"))
    )
    (net (code "51") (name "Net-(Q7-B)") (class "Default")
      (node (ref "Q7") (pin "1") (pinfunction "B_1") (pintype "passive"))
      (node (ref "R23") (pin "P$1") (pinfunction "1_P$1") (pintype "bidirectional"))
    )
    (net (code "52") (name "Net-(Q10-G)") (class "Default")
      (node (ref "Q10") (pin "1") (pinfunction "G_1") (pintype "bidirectional"))
      (node (ref "Q11") (pin "3") (pinfunction "C_3") (pintype "passive"))
      (node (ref "R15") (pin "P$1") (pinfunction "1_P$1") (pintype "bidirectional"))
    )
    (net (code "53") (name "Net-(Q11-B)") (class "Default")
      (node (ref "Q11") (pin "1") (pinfunction "B_1") (pintype "passive"))
      (node (ref "R22") (pin "P$1") (pinfunction "1_P$1") (pintype "bidirectional"))
    )
    (net (code "54") (name "Net-(R3-1)") (class "Default")
      (node (ref "R3") (pin "P$1") (pinfunction "1_P$1") (pintype "bidirectional"))
      (node (ref "R37") (pin "P$2") (pinfunction "2_P$2") (pintype "bidirectional"))
      (node (ref "R4") (pin "P$1") (pinfunction "1_P$1") (pintype "bidirectional"))
      (node (ref "U7") (pin "3") (pinfunction "A_3") (pintype "bidirectional"))
    )
    (net (code "55") (name "Net-(R6-2)") (class "Default")
      (node (ref "C4") (pin "2") (pinfunction "2_2") (pintype "passive"))
      (node (ref "R6") (pin "P$2") (pinfunction "2_P$2") (pintype "bidirectional"))
      (node (ref "U1") (pin "1") (pinfunction "LNA_IN_1") (pintype "bidirectional"))
    )
    (net (code "56") (name "Net-(R10-1)") (class "Default")
      (node (ref "PWR") (pin "+") (pinfunction "+_+") (pintype "passive"))
      (node (ref "R10") (pin "P$1") (pinfunction "1_P$1") (pintype "bidirectional"))
    )
    (net (code "57") (name "Net-(R31-2)") (class "Default")
      (node (ref "R31") (pin "P$2") (pinfunction "2_P$2") (pintype "bidirectional"))
      (node (ref "R40") (pin "P$1") (pinfunction "1_P$1") (pintype "bidirectional"))
      (node (ref "U2") (pin "5") (pinfunction "BF_5") (pintype "bidirectional"))
    )
    (net (code "58") (name "Net-(R37-1)") (class "Default")
      (node (ref "R37") (pin "P$1") (pinfunction "1_P$1") (pintype "bidirectional"))
      (node (ref "RGB1") (pin "1") (pinfunction "DI_1") (pintype "bidirectional"))
    )
    (net (code "59") (name "Net-(RGB1-DO)") (class "Default")
      (node (ref "RGB1") (pin "3") (pinfunction "DO_3") (pintype "bidirectional"))
      (node (ref "RGB2") (pin "1") (pinfunction "DI_1") (pintype "bidirectional"))
    )
    (net (code "60") (name "Net-(RGB2-DO)") (class "Default")
      (node (ref "RGB2") (pin "3") (pinfunction "DO_3") (pintype "bidirectional"))
      (node (ref "RGB3") (pin "1") (pinfunction "DI_1") (pintype "bidirectional"))
    )
    (net (code "61") (name "Net-(RGB3-DO)") (class "Default")
      (node (ref "RGB3") (pin "3") (pinfunction "DO_3") (pintype "bidirectional"))
      (node (ref "RGB4") (pin "1") (pinfunction "DI_1") (pintype "bidirectional"))
    )
    (net (code "62") (name "Net-(RGB4-DO)") (class "Default")
      (node (ref "RGB4") (pin "3") (pinfunction "DO_3") (pintype "bidirectional"))
      (node (ref "RGB5") (pin "1") (pinfunction "DI_1") (pintype "bidirectional"))
    )
    (net (code "63") (name "Net-(U$17-CLK)") (class "Default")
      (node (ref "U$17") (pin "6") (pinfunction "CLK_6") (pintype "bidirectional"))
      (node (ref "U1") (pin "33") (pinfunction "SPICLK_33") (pintype "bidirectional"))
    )
    (net (code "64") (name "Net-(U$17-DIMO)") (class "Default")
      (node (ref "U$17") (pin "5") (pinfunction "DIMO_5") (pintype "input"))
      (node (ref "U1") (pin "35") (pinfunction "SPI_MOSI_35") (pintype "bidirectional"))
    )
    (net (code "65") (name "Net-(U$17-{slash}HOLD)") (class "Default")
      (node (ref "U$17") (pin "7") (pinfunction "/HOLD_7") (pintype "bidirectional"))
      (node (ref "U1") (pin "30") (pinfunction "SPIHD_30") (pintype "bidirectional"))
    )
    (net (code "66") (name "Net-(U1-GP1O19{slash}USB_D-)") (class "Default")
      (node (ref "R43") (pin "2") (pinfunction "2_2") (pintype "passive"))
      (node (ref "U1") (pin "25") (pinfunction "GP1O19/USB_D-_25") (pintype "bidirectional"))
    )
    (net (code "67") (name "Net-(U1-GP1O20{slash}USB_D+)") (class "Default")
      (node (ref "R44") (pin "2") (pinfunction "2_2") (pintype "passive"))
      (node (ref "U1") (pin "26") (pinfunction "GP1O20/USB_D+_26") (pintype "bidirectional"))
    )
    (net (code "68") (name "Net-(U1-XTAL_N)") (class "Default")
      (node (ref "C9") (pin "1") (pinfunction "1_1") (pintype "passive"))
      (node (ref "U1") (pin "54") (pinfunction "XTAL_N_54") (pintype "bidirectional"))
      (node (ref "Y1") (pin "1") (pinfunction "C1_1") (pintype "passive"))
    )
    (net (code "69") (name "Net-(U1-XTAL_P)") (class "Default")
      (node (ref "C13") (pin "1") (pinfunction "1_1") (pintype "passive"))
      (node (ref "U1") (pin "53") (pinfunction "XTAL_P_53") (pintype "bidirectional"))
      (node (ref "Y1") (pin "3") (pinfunction "C2_3") (pintype "passive"))
    )
    (net (code "70") (name "Net-(U2-LX)") (class "Default")
      (node (ref "L3") (pin "1") (pinfunction "1_1") (pintype "passive"))
      (node (ref "U2") (pin "3") (pinfunction "LX_3") (pintype "bidirectional"))
    )
    (net (code "71") (name "unconnected-(RGB5-DO-Pad3)") (class "Default")
      (node (ref "RGB5") (pin "3") (pinfunction "DO_3") (pintype "bidirectional"))
    )
    (net (code "72") (name "unconnected-(U$30-PadP$1)") (class "Default")
      (node (ref "U$30") (pin "P$1") (pinfunction "P$1_P$1") (pintype "bidirectional"))
    )
    (net (code "73") (name "unconnected-(U1-GP1O8-Pad13)") (class "Default")
      (node (ref "U1") (pin "13") (pinfunction "GP1O8_13") (pintype "bidirectional"))
    )
    (net (code "74") (name "unconnected-(U1-GP1O17-Pad23)") (class "Default")
      (node (ref "U1") (pin "23") (pinfunction "GP1O17_23") (pintype "bidirectional"))
    )
    (net (code "75") (name "unconnected-(U1-GP1O18-Pad24)") (class "Default")
      (node (ref "U1") (pin "24") (pinfunction "GP1O18_24") (pintype "bidirectional"))
    )
    (net (code "76") (name "unconnected-(U1-GP1O21-Pad27)") (class "Default")
      (node (ref "U1") (pin "27") (pinfunction "GP1O21_27") (pintype "bidirectional"))
    )
    (net (code "77") (name "unconnected-(U1-GP1O33-Pad38)") (class "Default")
      (node (ref "U1") (pin "38") (pinfunction "GP1O33_38") (pintype "bidirectional"))
    )
    (net (code "78") (name "unconnected-(U1-GP1O34-Pad39)") (class "Default")
      (node (ref "U1") (pin "39") (pinfunction "GP1O34_39") (pintype "bidirectional"))
    )
    (net (code "79") (name "unconnected-(U1-GP1O35-Pad40)") (class "Default")
      (node (ref "U1") (pin "40") (pinfunction "GP1O35_40") (pintype "bidirectional"))
    )
    (net (code "80") (name "unconnected-(U1-GP1O36-Pad41)") (class "Default")
      (node (ref "U1") (pin "41") (pinfunction "GP1O36_41") (pintype "bidirectional"))
    )
    (net (code "81") (name "unconnected-(U1-GP1O37-Pad42)") (class "Default")
      (node (ref "U1") (pin "42") (pinfunction "GP1O37_42") (pintype "bidirectional"))
    )
    (net (code "82") (name "unconnected-(U1-SPICS1-Pad28)") (class "Default")
      (node (ref "U1") (pin "28") (pinfunction "SPICS1_28") (pintype "bidirectional"))
    )
    (net (code "83") (name "unconnected-(U1-XTAL_32K_N-Pad22)") (class "Default")
      (node (ref "U1") (pin "22") (pinfunction "XTAL_32K_N_22") (pintype "bidirectional"))
    )
    (net (code "84") (name "unconnected-(U1-XTAL_32K_P-Pad21)") (class "Default")
      (node (ref "U1") (pin "21") (pinfunction "XTAL_32K_P_21") (pintype "bidirectional"))
    )
  )
)
